# Backplane.net
KiCad netlist of a schematic drawn in EAGLE
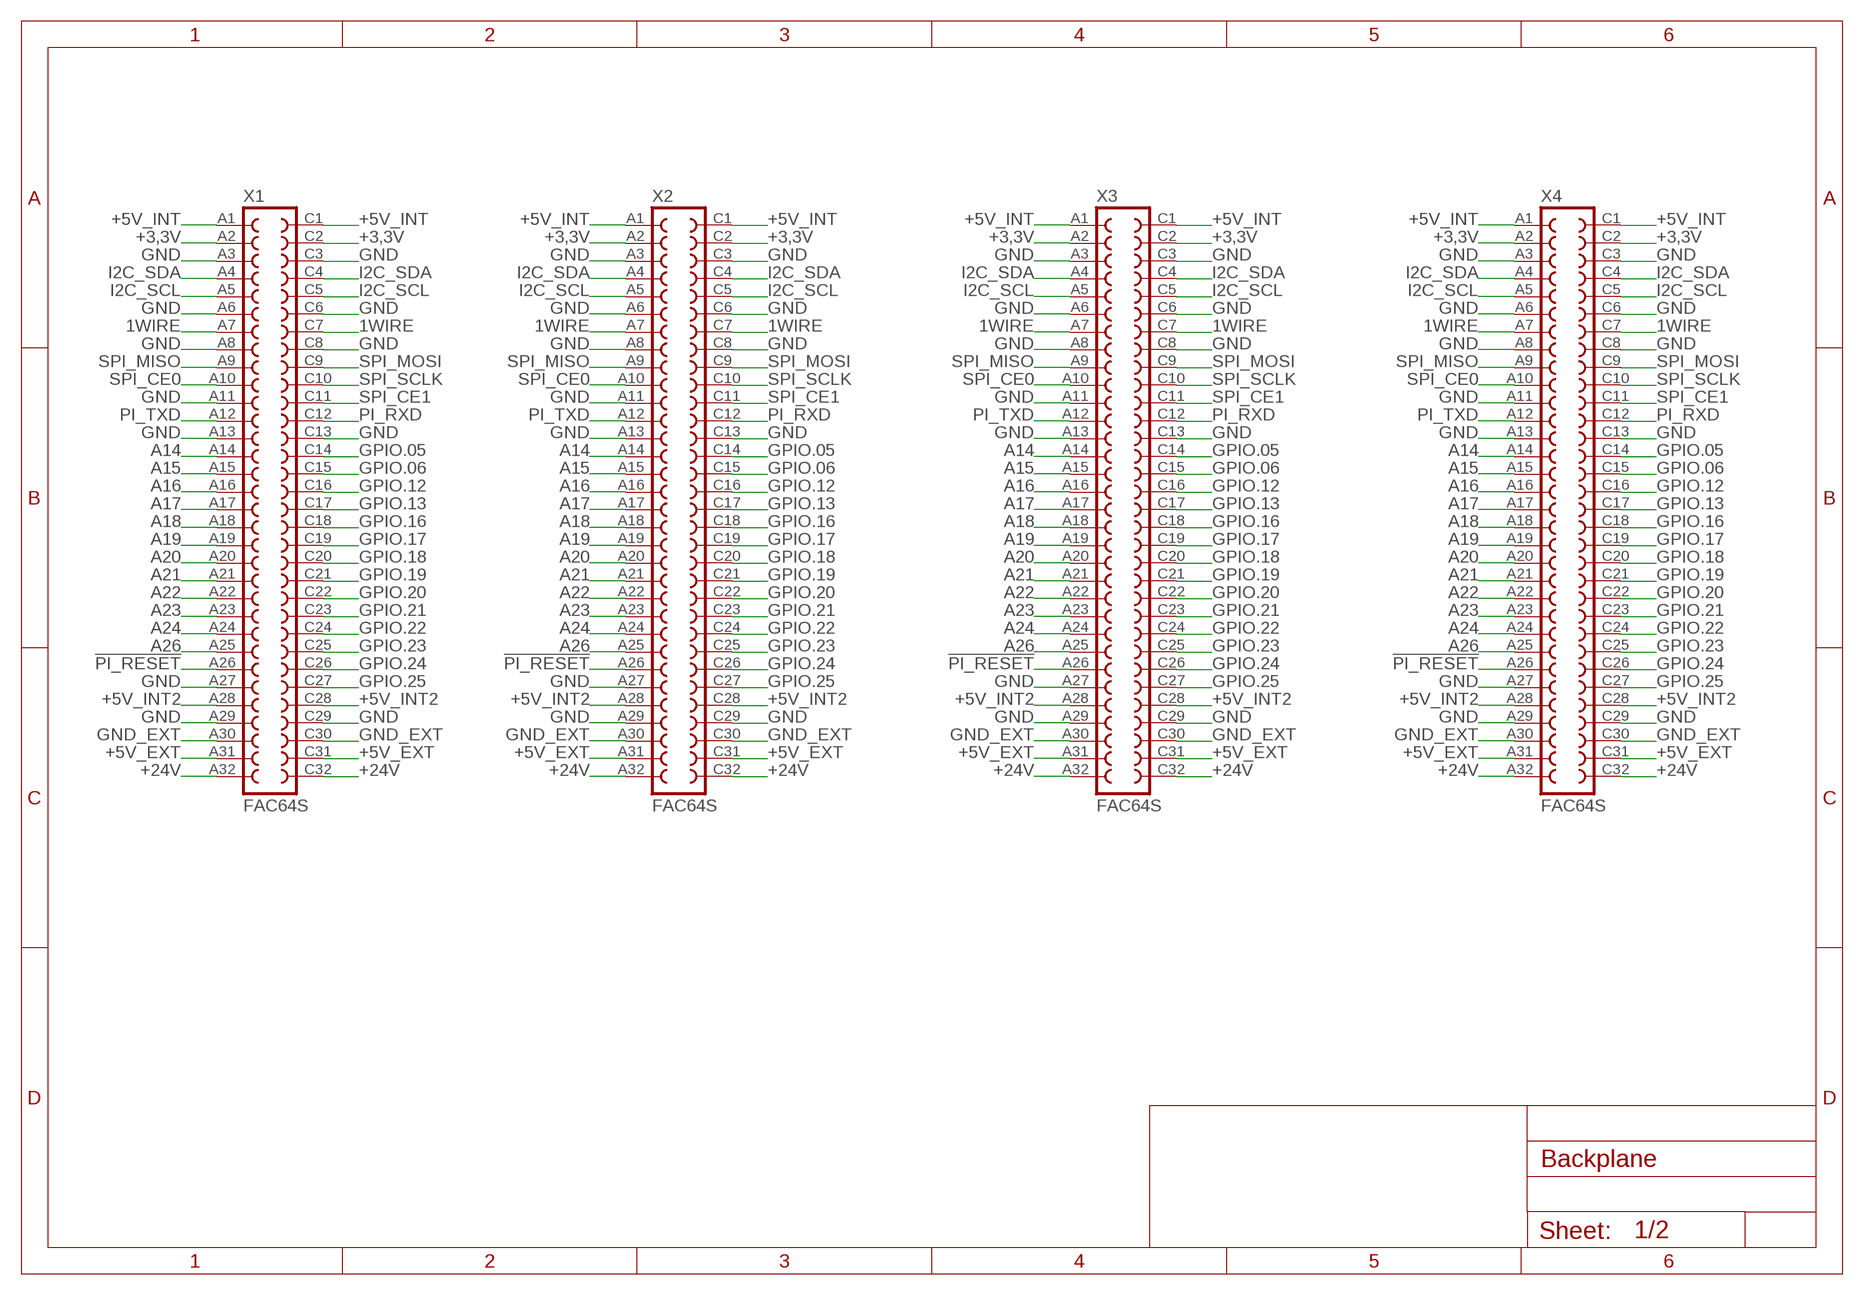
[diagram p0: schematic, sheet 1]
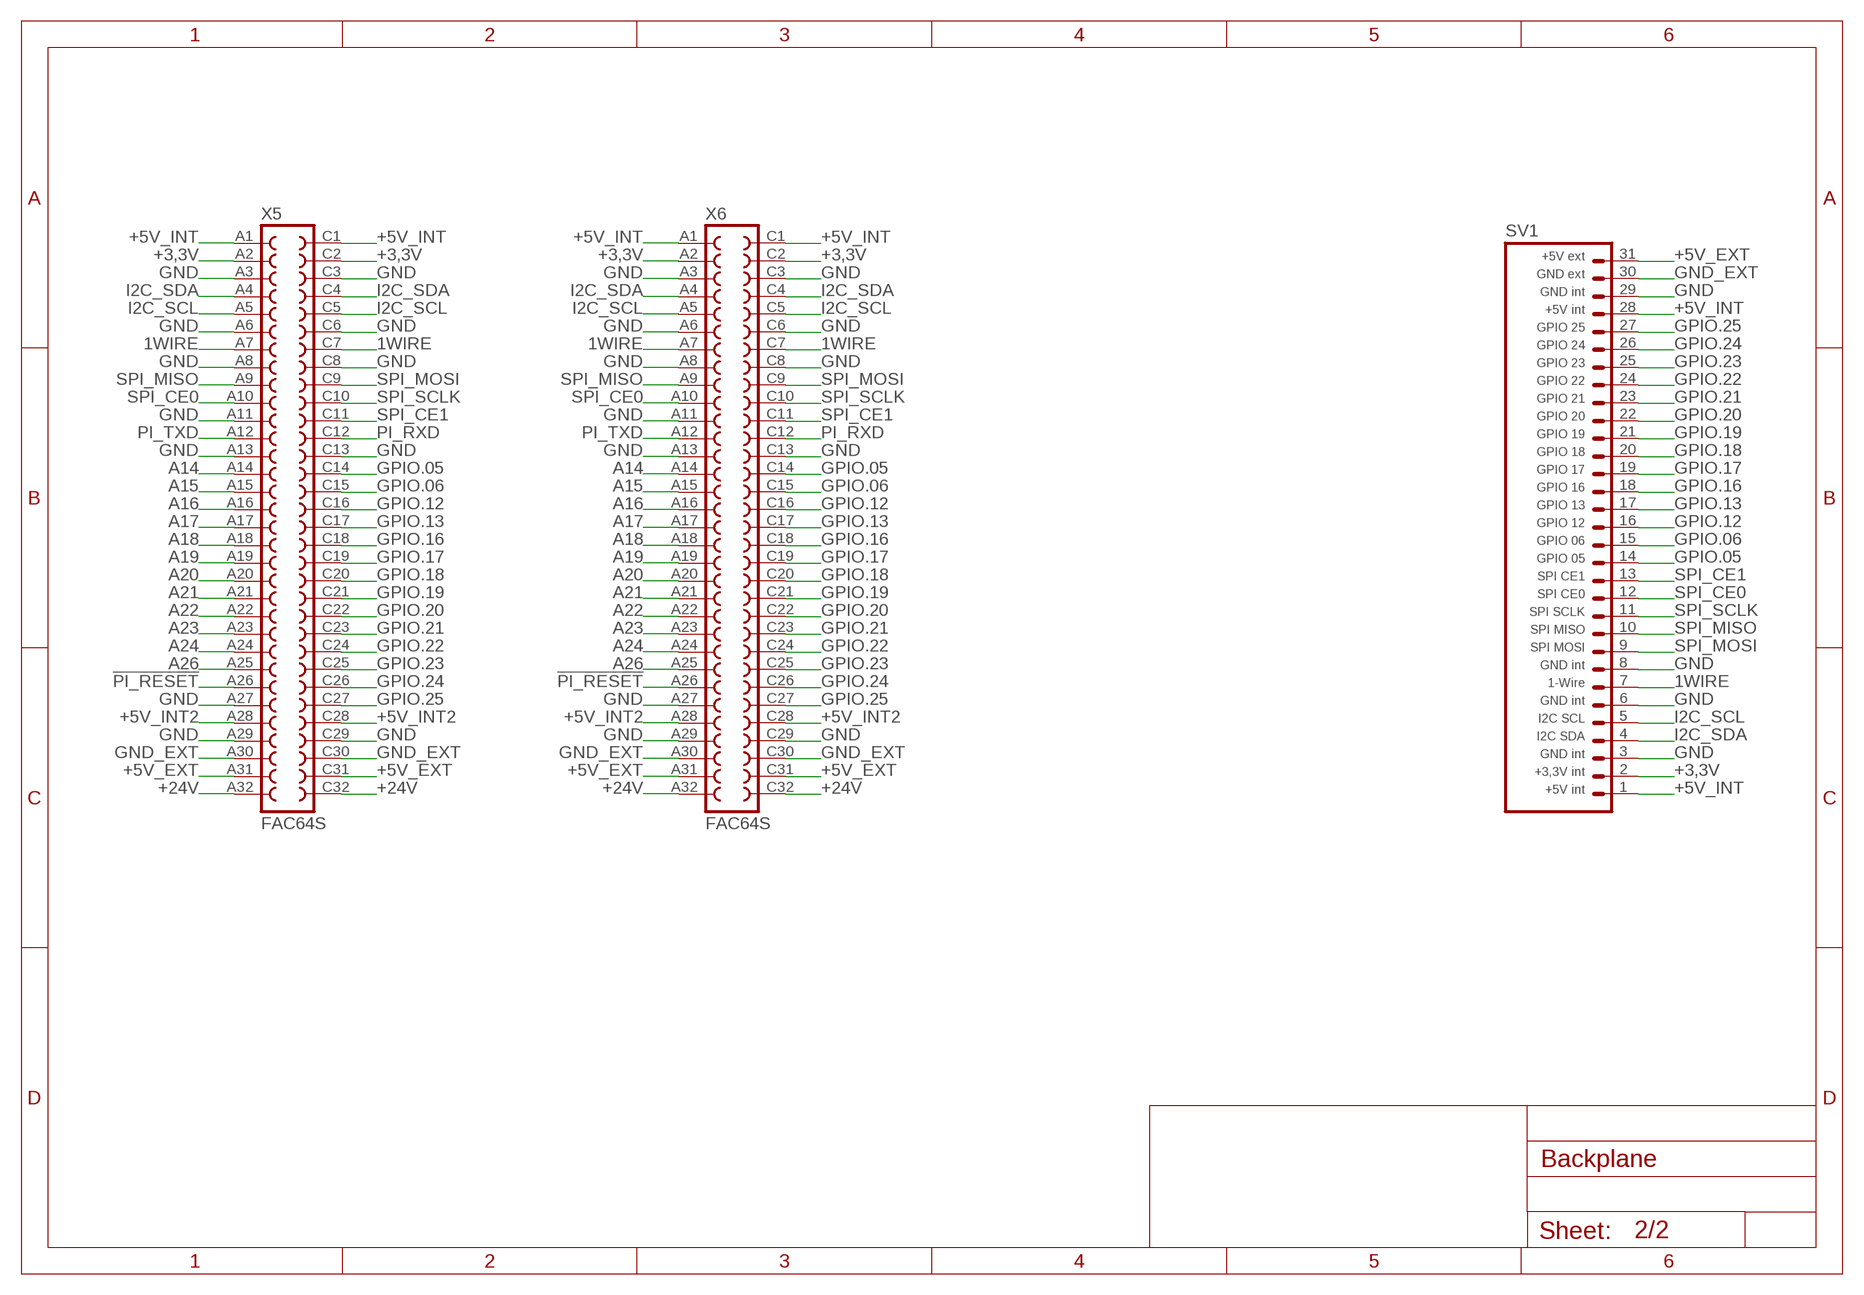
[diagram p1: schematic, sheet 2]

(export (version "E")
  (design (tool "Eeschema 10.0.6"))
  (components
    (comp (ref "X1")
      (value "FAC64S")
      (footprint "eagle-import:FAC64S")
      (libsource (lib "eagle-import") (part "FAC64S"))
    )
    (comp (ref "X2")
      (value "FAC64S")
      (footprint "eagle-import:FAC64S")
      (libsource (lib "eagle-import") (part "FAC64S"))
    )
    (comp (ref "X3")
      (value "FAC64S")
      (footprint "eagle-import:FAC64S")
      (libsource (lib "eagle-import") (part "FAC64S"))
    )
    (comp (ref "X4")
      (value "FAC64S")
      (footprint "eagle-import:FAC64S")
      (libsource (lib "eagle-import") (part "FAC64S"))
    )
    (comp (ref "SV1")
      (value "PLATINENVERBINDER-31SMD-BOTTOM")
      (footprint "eagle-import:PLATINENVERBINDER-31-SMD_BOTTOM")
      (libsource (lib "eagle-import") (part "PLATINENVERBINDER-31SMD-BOTTOM"))
    )
    (comp (ref "X5")
      (value "FAC64S")
      (footprint "eagle-import:FAC64S")
      (libsource (lib "eagle-import") (part "FAC64S"))
    )
    (comp (ref "X6")
      (value "FAC64S")
      (footprint "eagle-import:FAC64S")
      (libsource (lib "eagle-import") (part "FAC64S"))
    )
  )
  (nets
    (net (code "1") (name "+3,3V") (class "Default")
      (node (ref "SV1") (pin "2") (pinfunction "2_2") (pintype "passive"))
      (node (ref "X1") (pin "A2") (pinfunction "A2_A2") (pintype "passive"))
      (node (ref "X1") (pin "C2") (pinfunction "C2_C2") (pintype "passive"))
      (node (ref "X2") (pin "A2") (pinfunction "A2_A2") (pintype "passive"))
      (node (ref "X2") (pin "C2") (pinfunction "C2_C2") (pintype "passive"))
      (node (ref "X3") (pin "A2") (pinfunction "A2_A2") (pintype "passive"))
      (node (ref "X3") (pin "C2") (pinfunction "C2_C2") (pintype "passive"))
      (node (ref "X4") (pin "A2") (pinfunction "A2_A2") (pintype "passive"))
      (node (ref "X4") (pin "C2") (pinfunction "C2_C2") (pintype "passive"))
      (node (ref "X5") (pin "A2") (pinfunction "A2_A2") (pintype "passive"))
      (node (ref "X5") (pin "C2") (pinfunction "C2_C2") (pintype "passive"))
      (node (ref "X6") (pin "A2") (pinfunction "A2_A2") (pintype "passive"))
      (node (ref "X6") (pin "C2") (pinfunction "C2_C2") (pintype "passive"))
    )
    (net (code "2") (name "+5V_EXT") (class "Default")
      (node (ref "SV1") (pin "31") (pinfunction "31_31") (pintype "passive"))
      (node (ref "X1") (pin "A31") (pinfunction "A31_A31") (pintype "passive"))
      (node (ref "X1") (pin "C31") (pinfunction "C31_C31") (pintype "passive"))
      (node (ref "X2") (pin "A31") (pinfunction "A31_A31") (pintype "passive"))
      (node (ref "X2") (pin "C31") (pinfunction "C31_C31") (pintype "passive"))
      (node (ref "X3") (pin "A31") (pinfunction "A31_A31") (pintype "passive"))
      (node (ref "X3") (pin "C31") (pinfunction "C31_C31") (pintype "passive"))
      (node (ref "X4") (pin "A31") (pinfunction "A31_A31") (pintype "passive"))
      (node (ref "X4") (pin "C31") (pinfunction "C31_C31") (pintype "passive"))
      (node (ref "X5") (pin "A31") (pinfunction "A31_A31") (pintype "passive"))
      (node (ref "X5") (pin "C31") (pinfunction "C31_C31") (pintype "passive"))
      (node (ref "X6") (pin "A31") (pinfunction "A31_A31") (pintype "passive"))
      (node (ref "X6") (pin "C31") (pinfunction "C31_C31") (pintype "passive"))
    )
    (net (code "3") (name "+5V_INT") (class "Default")
      (node (ref "SV1") (pin "1") (pinfunction "1_1") (pintype "passive"))
      (node (ref "SV1") (pin "28") (pinfunction "28_28") (pintype "passive"))
      (node (ref "X1") (pin "A1") (pinfunction "A1_A1") (pintype "passive"))
      (node (ref "X1") (pin "C1") (pinfunction "C1_C1") (pintype "passive"))
      (node (ref "X2") (pin "A1") (pinfunction "A1_A1") (pintype "passive"))
      (node (ref "X2") (pin "C1") (pinfunction "C1_C1") (pintype "passive"))
      (node (ref "X3") (pin "A1") (pinfunction "A1_A1") (pintype "passive"))
      (node (ref "X3") (pin "C1") (pinfunction "C1_C1") (pintype "passive"))
      (node (ref "X4") (pin "A1") (pinfunction "A1_A1") (pintype "passive"))
      (node (ref "X4") (pin "C1") (pinfunction "C1_C1") (pintype "passive"))
      (node (ref "X5") (pin "A1") (pinfunction "A1_A1") (pintype "passive"))
      (node (ref "X5") (pin "C1") (pinfunction "C1_C1") (pintype "passive"))
      (node (ref "X6") (pin "A1") (pinfunction "A1_A1") (pintype "passive"))
      (node (ref "X6") (pin "C1") (pinfunction "C1_C1") (pintype "passive"))
    )
    (net (code "4") (name "+5V_INT2") (class "Default")
      (node (ref "X1") (pin "A28") (pinfunction "A28_A28") (pintype "passive"))
      (node (ref "X1") (pin "C28") (pinfunction "C28_C28") (pintype "passive"))
      (node (ref "X2") (pin "A28") (pinfunction "A28_A28") (pintype "passive"))
      (node (ref "X2") (pin "C28") (pinfunction "C28_C28") (pintype "passive"))
      (node (ref "X3") (pin "A28") (pinfunction "A28_A28") (pintype "passive"))
      (node (ref "X3") (pin "C28") (pinfunction "C28_C28") (pintype "passive"))
      (node (ref "X4") (pin "A28") (pinfunction "A28_A28") (pintype "passive"))
      (node (ref "X4") (pin "C28") (pinfunction "C28_C28") (pintype "passive"))
      (node (ref "X5") (pin "A28") (pinfunction "A28_A28") (pintype "passive"))
      (node (ref "X5") (pin "C28") (pinfunction "C28_C28") (pintype "passive"))
      (node (ref "X6") (pin "A28") (pinfunction "A28_A28") (pintype "passive"))
      (node (ref "X6") (pin "C28") (pinfunction "C28_C28") (pintype "passive"))
    )
    (net (code "5") (name "+24V") (class "Default")
      (node (ref "X1") (pin "A32") (pinfunction "A32_A32") (pintype "passive"))
      (node (ref "X1") (pin "C32") (pinfunction "C32_C32") (pintype "passive"))
      (node (ref "X2") (pin "A32") (pinfunction "A32_A32") (pintype "passive"))
      (node (ref "X2") (pin "C32") (pinfunction "C32_C32") (pintype "passive"))
      (node (ref "X3") (pin "A32") (pinfunction "A32_A32") (pintype "passive"))
      (node (ref "X3") (pin "C32") (pinfunction "C32_C32") (pintype "passive"))
      (node (ref "X4") (pin "A32") (pinfunction "A32_A32") (pintype "passive"))
      (node (ref "X4") (pin "C32") (pinfunction "C32_C32") (pintype "passive"))
      (node (ref "X5") (pin "A32") (pinfunction "A32_A32") (pintype "passive"))
      (node (ref "X5") (pin "C32") (pinfunction "C32_C32") (pintype "passive"))
      (node (ref "X6") (pin "A32") (pinfunction "A32_A32") (pintype "passive"))
      (node (ref "X6") (pin "C32") (pinfunction "C32_C32") (pintype "passive"))
    )
    (net (code "6") (name "1WIRE") (class "Default")
      (node (ref "SV1") (pin "7") (pinfunction "7_7") (pintype "passive"))
      (node (ref "X1") (pin "A7") (pinfunction "A7_A7") (pintype "passive"))
      (node (ref "X1") (pin "C7") (pinfunction "C7_C7") (pintype "passive"))
      (node (ref "X2") (pin "A7") (pinfunction "A7_A7") (pintype "passive"))
      (node (ref "X2") (pin "C7") (pinfunction "C7_C7") (pintype "passive"))
      (node (ref "X3") (pin "A7") (pinfunction "A7_A7") (pintype "passive"))
      (node (ref "X3") (pin "C7") (pinfunction "C7_C7") (pintype "passive"))
      (node (ref "X4") (pin "A7") (pinfunction "A7_A7") (pintype "passive"))
      (node (ref "X4") (pin "C7") (pinfunction "C7_C7") (pintype "passive"))
      (node (ref "X5") (pin "A7") (pinfunction "A7_A7") (pintype "passive"))
      (node (ref "X5") (pin "C7") (pinfunction "C7_C7") (pintype "passive"))
      (node (ref "X6") (pin "A7") (pinfunction "A7_A7") (pintype "passive"))
      (node (ref "X6") (pin "C7") (pinfunction "C7_C7") (pintype "passive"))
    )
    (net (code "7") (name "A14") (class "Default")
      (node (ref "X1") (pin "A14") (pinfunction "A14_A14") (pintype "passive"))
      (node (ref "X2") (pin "A14") (pinfunction "A14_A14") (pintype "passive"))
      (node (ref "X3") (pin "A14") (pinfunction "A14_A14") (pintype "passive"))
      (node (ref "X4") (pin "A14") (pinfunction "A14_A14") (pintype "passive"))
      (node (ref "X5") (pin "A14") (pinfunction "A14_A14") (pintype "passive"))
      (node (ref "X6") (pin "A14") (pinfunction "A14_A14") (pintype "passive"))
    )
    (net (code "8") (name "A15") (class "Default")
      (node (ref "X1") (pin "A15") (pinfunction "A15_A15") (pintype "passive"))
      (node (ref "X2") (pin "A15") (pinfunction "A15_A15") (pintype "passive"))
      (node (ref "X3") (pin "A15") (pinfunction "A15_A15") (pintype "passive"))
      (node (ref "X4") (pin "A15") (pinfunction "A15_A15") (pintype "passive"))
      (node (ref "X5") (pin "A15") (pinfunction "A15_A15") (pintype "passive"))
      (node (ref "X6") (pin "A15") (pinfunction "A15_A15") (pintype "passive"))
    )
    (net (code "9") (name "A16") (class "Default")
      (node (ref "X1") (pin "A16") (pinfunction "A16_A16") (pintype "passive"))
      (node (ref "X2") (pin "A16") (pinfunction "A16_A16") (pintype "passive"))
      (node (ref "X3") (pin "A16") (pinfunction "A16_A16") (pintype "passive"))
      (node (ref "X4") (pin "A16") (pinfunction "A16_A16") (pintype "passive"))
      (node (ref "X5") (pin "A16") (pinfunction "A16_A16") (pintype "passive"))
      (node (ref "X6") (pin "A16") (pinfunction "A16_A16") (pintype "passive"))
    )
    (net (code "10") (name "A17") (class "Default")
      (node (ref "X1") (pin "A17") (pinfunction "A17_A17") (pintype "passive"))
      (node (ref "X2") (pin "A17") (pinfunction "A17_A17") (pintype "passive"))
      (node (ref "X3") (pin "A17") (pinfunction "A17_A17") (pintype "passive"))
      (node (ref "X4") (pin "A17") (pinfunction "A17_A17") (pintype "passive"))
      (node (ref "X5") (pin "A17") (pinfunction "A17_A17") (pintype "passive"))
      (node (ref "X6") (pin "A17") (pinfunction "A17_A17") (pintype "passive"))
    )
    (net (code "11") (name "A18") (class "Default")
      (node (ref "X1") (pin "A18") (pinfunction "A18_A18") (pintype "passive"))
      (node (ref "X2") (pin "A18") (pinfunction "A18_A18") (pintype "passive"))
      (node (ref "X3") (pin "A18") (pinfunction "A18_A18") (pintype "passive"))
      (node (ref "X4") (pin "A18") (pinfunction "A18_A18") (pintype "passive"))
      (node (ref "X5") (pin "A18") (pinfunction "A18_A18") (pintype "passive"))
      (node (ref "X6") (pin "A18") (pinfunction "A18_A18") (pintype "passive"))
    )
    (net (code "12") (name "A19") (class "Default")
      (node (ref "X1") (pin "A19") (pinfunction "A19_A19") (pintype "passive"))
      (node (ref "X2") (pin "A19") (pinfunction "A19_A19") (pintype "passive"))
      (node (ref "X3") (pin "A19") (pinfunction "A19_A19") (pintype "passive"))
      (node (ref "X4") (pin "A19") (pinfunction "A19_A19") (pintype "passive"))
      (node (ref "X5") (pin "A19") (pinfunction "A19_A19") (pintype "passive"))
      (node (ref "X6") (pin "A19") (pinfunction "A19_A19") (pintype "passive"))
    )
    (net (code "13") (name "A20") (class "Default")
      (node (ref "X1") (pin "A20") (pinfunction "A20_A20") (pintype "passive"))
      (node (ref "X2") (pin "A20") (pinfunction "A20_A20") (pintype "passive"))
      (node (ref "X3") (pin "A20") (pinfunction "A20_A20") (pintype "passive"))
      (node (ref "X4") (pin "A20") (pinfunction "A20_A20") (pintype "passive"))
      (node (ref "X5") (pin "A20") (pinfunction "A20_A20") (pintype "passive"))
      (node (ref "X6") (pin "A20") (pinfunction "A20_A20") (pintype "passive"))
    )
    (net (code "14") (name "A21") (class "Default")
      (node (ref "X1") (pin "A21") (pinfunction "A21_A21") (pintype "passive"))
      (node (ref "X2") (pin "A21") (pinfunction "A21_A21") (pintype "passive"))
      (node (ref "X3") (pin "A21") (pinfunction "A21_A21") (pintype "passive"))
      (node (ref "X4") (pin "A21") (pinfunction "A21_A21") (pintype "passive"))
      (node (ref "X5") (pin "A21") (pinfunction "A21_A21") (pintype "passive"))
      (node (ref "X6") (pin "A21") (pinfunction "A21_A21") (pintype "passive"))
    )
    (net (code "15") (name "A22") (class "Default")
      (node (ref "X1") (pin "A22") (pinfunction "A22_A22") (pintype "passive"))
      (node (ref "X2") (pin "A22") (pinfunction "A22_A22") (pintype "passive"))
      (node (ref "X3") (pin "A22") (pinfunction "A22_A22") (pintype "passive"))
      (node (ref "X4") (pin "A22") (pinfunction "A22_A22") (pintype "passive"))
      (node (ref "X5") (pin "A22") (pinfunction "A22_A22") (pintype "passive"))
      (node (ref "X6") (pin "A22") (pinfunction "A22_A22") (pintype "passive"))
    )
    (net (code "16") (name "A23") (class "Default")
      (node (ref "X1") (pin "A23") (pinfunction "A23_A23") (pintype "passive"))
      (node (ref "X2") (pin "A23") (pinfunction "A23_A23") (pintype "passive"))
      (node (ref "X3") (pin "A23") (pinfunction "A23_A23") (pintype "passive"))
      (node (ref "X4") (pin "A23") (pinfunction "A23_A23") (pintype "passive"))
      (node (ref "X5") (pin "A23") (pinfunction "A23_A23") (pintype "passive"))
      (node (ref "X6") (pin "A23") (pinfunction "A23_A23") (pintype "passive"))
    )
    (net (code "17") (name "A24") (class "Default")
      (node (ref "X1") (pin "A24") (pinfunction "A24_A24") (pintype "passive"))
      (node (ref "X2") (pin "A24") (pinfunction "A24_A24") (pintype "passive"))
      (node (ref "X3") (pin "A24") (pinfunction "A24_A24") (pintype "passive"))
      (node (ref "X4") (pin "A24") (pinfunction "A24_A24") (pintype "passive"))
      (node (ref "X5") (pin "A24") (pinfunction "A24_A24") (pintype "passive"))
      (node (ref "X6") (pin "A24") (pinfunction "A24_A24") (pintype "passive"))
    )
    (net (code "18") (name "A26") (class "Default")
      (node (ref "X1") (pin "A25") (pinfunction "A25_A25") (pintype "passive"))
      (node (ref "X2") (pin "A25") (pinfunction "A25_A25") (pintype "passive"))
      (node (ref "X3") (pin "A25") (pinfunction "A25_A25") (pintype "passive"))
      (node (ref "X4") (pin "A25") (pinfunction "A25_A25") (pintype "passive"))
      (node (ref "X5") (pin "A25") (pinfunction "A25_A25") (pintype "passive"))
      (node (ref "X6") (pin "A25") (pinfunction "A25_A25") (pintype "passive"))
    )
    (net (code "19") (name "GND") (class "Default")
      (node (ref "SV1") (pin "29") (pinfunction "29_29") (pintype "passive"))
      (node (ref "SV1") (pin "3") (pinfunction "3_3") (pintype "passive"))
      (node (ref "SV1") (pin "6") (pinfunction "6_6") (pintype "passive"))
      (node (ref "SV1") (pin "8") (pinfunction "8_8") (pintype "passive"))
      (node (ref "X1") (pin "A11") (pinfunction "A11_A11") (pintype "passive"))
      (node (ref "X1") (pin "A13") (pinfunction "A13_A13") (pintype "passive"))
      (node (ref "X1") (pin "A27") (pinfunction "A27_A27") (pintype "passive"))
      (node (ref "X1") (pin "A29") (pinfunction "A29_A29") (pintype "passive"))
      (node (ref "X1") (pin "A3") (pinfunction "A3_A3") (pintype "passive"))
      (node (ref "X1") (pin "A6") (pinfunction "A6_A6") (pintype "passive"))
      (node (ref "X1") (pin "A8") (pinfunction "A8_A8") (pintype "passive"))
      (node (ref "X1") (pin "C13") (pinfunction "C13_C13") (pintype "passive"))
      (node (ref "X1") (pin "C29") (pinfunction "C29_C29") (pintype "passive"))
      (node (ref "X1") (pin "C3") (pinfunction "C3_C3") (pintype "passive"))
      (node (ref "X1") (pin "C6") (pinfunction "C6_C6") (pintype "passive"))
      (node (ref "X1") (pin "C8") (pinfunction "C8_C8") (pintype "passive"))
      (node (ref "X2") (pin "A11") (pinfunction "A11_A11") (pintype "passive"))
      (node (ref "X2") (pin "A13") (pinfunction "A13_A13") (pintype "passive"))
      (node (ref "X2") (pin "A27") (pinfunction "A27_A27") (pintype "passive"))
      (node (ref "X2") (pin "A29") (pinfunction "A29_A29") (pintype "passive"))
      (node (ref "X2") (pin "A3") (pinfunction "A3_A3") (pintype "passive"))
      (node (ref "X2") (pin "A6") (pinfunction "A6_A6") (pintype "passive"))
      (node (ref "X2") (pin "A8") (pinfunction "A8_A8") (pintype "passive"))
      (node (ref "X2") (pin "C13") (pinfunction "C13_C13") (pintype "passive"))
      (node (ref "X2") (pin "C29") (pinfunction "C29_C29") (pintype "passive"))
      (node (ref "X2") (pin "C3") (pinfunction "C3_C3") (pintype "passive"))
      (node (ref "X2") (pin "C6") (pinfunction "C6_C6") (pintype "passive"))
      (node (ref "X2") (pin "C8") (pinfunction "C8_C8") (pintype "passive"))
      (node (ref "X3") (pin "A11") (pinfunction "A11_A11") (pintype "passive"))
      (node (ref "X3") (pin "A13") (pinfunction "A13_A13") (pintype "passive"))
      (node (ref "X3") (pin "A27") (pinfunction "A27_A27") (pintype "passive"))
      (node (ref "X3") (pin "A29") (pinfunction "A29_A29") (pintype "passive"))
      (node (ref "X3") (pin "A3") (pinfunction "A3_A3") (pintype "passive"))
      (node (ref "X3") (pin "A6") (pinfunction "A6_A6") (pintype "passive"))
      (node (ref "X3") (pin "A8") (pinfunction "A8_A8") (pintype "passive"))
      (node (ref "X3") (pin "C13") (pinfunction "C13_C13") (pintype "passive"))
      (node (ref "X3") (pin "C29") (pinfunction "C29_C29") (pintype "passive"))
      (node (ref "X3") (pin "C3") (pinfunction "C3_C3") (pintype "passive"))
      (node (ref "X3") (pin "C6") (pinfunction "C6_C6") (pintype "passive"))
      (node (ref "X3") (pin "C8") (pinfunction "C8_C8") (pintype "passive"))
      (node (ref "X4") (pin "A11") (pinfunction "A11_A11") (pintype "passive"))
      (node (ref "X4") (pin "A13") (pinfunction "A13_A13") (pintype "passive"))
      (node (ref "X4") (pin "A27") (pinfunction "A27_A27") (pintype "passive"))
      (node (ref "X4") (pin "A29") (pinfunction "A29_A29") (pintype "passive"))
      (node (ref "X4") (pin "A3") (pinfunction "A3_A3") (pintype "passive"))
      (node (ref "X4") (pin "A6") (pinfunction "A6_A6") (pintype "passive"))
      (node (ref "X4") (pin "A8") (pinfunction "A8_A8") (pintype "passive"))
      (node (ref "X4") (pin "C13") (pinfunction "C13_C13") (pintype "passive"))
      (node (ref "X4") (pin "C29") (pinfunction "C29_C29") (pintype "passive"))
      (node (ref "X4") (pin "C3") (pinfunction "C3_C3") (pintype "passive"))
      (node (ref "X4") (pin "C6") (pinfunction "C6_C6") (pintype "passive"))
      (node (ref "X4") (pin "C8") (pinfunction "C8_C8") (pintype "passive"))
      (node (ref "X5") (pin "A11") (pinfunction "A11_A11") (pintype "passive"))
      (node (ref "X5") (pin "A13") (pinfunction "A13_A13") (pintype "passive"))
      (node (ref "X5") (pin "A27") (pinfunction "A27_A27") (pintype "passive"))
      (node (ref "X5") (pin "A29") (pinfunction "A29_A29") (pintype "passive"))
      (node (ref "X5") (pin "A3") (pinfunction "A3_A3") (pintype "passive"))
      (node (ref "X5") (pin "A6") (pinfunction "A6_A6") (pintype "passive"))
      (node (ref "X5") (pin "A8") (pinfunction "A8_A8") (pintype "passive"))
      (node (ref "X5") (pin "C13") (pinfunction "C13_C13") (pintype "passive"))
      (node (ref "X5") (pin "C29") (pinfunction "C29_C29") (pintype "passive"))
      (node (ref "X5") (pin "C3") (pinfunction "C3_C3") (pintype "passive"))
      (node (ref "X5") (pin "C6") (pinfunction "C6_C6") (pintype "passive"))
      (node (ref "X5") (pin "C8") (pinfunction "C8_C8") (pintype "passive"))
      (node (ref "X6") (pin "A11") (pinfunction "A11_A11") (pintype "passive"))
      (node (ref "X6") (pin "A13") (pinfunction "A13_A13") (pintype "passive"))
      (node (ref "X6") (pin "A27") (pinfunction "A27_A27") (pintype "passive"))
      (node (ref "X6") (pin "A29") (pinfunction "A29_A29") (pintype "passive"))
      (node (ref "X6") (pin "A3") (pinfunction "A3_A3") (pintype "passive"))
      (node (ref "X6") (pin "A6") (pinfunction "A6_A6") (pintype "passive"))
      (node (ref "X6") (pin "A8") (pinfunction "A8_A8") (pintype "passive"))
      (node (ref "X6") (pin "C13") (pinfunction "C13_C13") (pintype "passive"))
      (node (ref "X6") (pin "C29") (pinfunction "C29_C29") (pintype "passive"))
      (node (ref "X6") (pin "C3") (pinfunction "C3_C3") (pintype "passive"))
      (node (ref "X6") (pin "C6") (pinfunction "C6_C6") (pintype "passive"))
      (node (ref "X6") (pin "C8") (pinfunction "C8_C8") (pintype "passive"))
    )
    (net (code "20") (name "GND_EXT") (class "Default")
      (node (ref "SV1") (pin "30") (pinfunction "30_30") (pintype "passive"))
      (node (ref "X1") (pin "A30") (pinfunction "A30_A30") (pintype "passive"))
      (node (ref "X1") (pin "C30") (pinfunction "C30_C30") (pintype "passive"))
      (node (ref "X2") (pin "A30") (pinfunction "A30_A30") (pintype "passive"))
      (node (ref "X2") (pin "C30") (pinfunction "C30_C30") (pintype "passive"))
      (node (ref "X3") (pin "A30") (pinfunction "A30_A30") (pintype "passive"))
      (node (ref "X3") (pin "C30") (pinfunction "C30_C30") (pintype "passive"))
      (node (ref "X4") (pin "A30") (pinfunction "A30_A30") (pintype "passive"))
      (node (ref "X4") (pin "C30") (pinfunction "C30_C30") (pintype "passive"))
      (node (ref "X5") (pin "A30") (pinfunction "A30_A30") (pintype "passive"))
      (node (ref "X5") (pin "C30") (pinfunction "C30_C30") (pintype "passive"))
      (node (ref "X6") (pin "A30") (pinfunction "A30_A30") (pintype "passive"))
      (node (ref "X6") (pin "C30") (pinfunction "C30_C30") (pintype "passive"))
    )
    (net (code "21") (name "GPIO.05") (class "Default")
      (node (ref "SV1") (pin "14") (pinfunction "14_14") (pintype "passive"))
      (node (ref "X1") (pin "C14") (pinfunction "C14_C14") (pintype "passive"))
      (node (ref "X2") (pin "C14") (pinfunction "C14_C14") (pintype "passive"))
      (node (ref "X3") (pin "C14") (pinfunction "C14_C14") (pintype "passive"))
      (node (ref "X4") (pin "C14") (pinfunction "C14_C14") (pintype "passive"))
      (node (ref "X5") (pin "C14") (pinfunction "C14_C14") (pintype "passive"))
      (node (ref "X6") (pin "C14") (pinfunction "C14_C14") (pintype "passive"))
    )
    (net (code "22") (name "GPIO.06") (class "Default")
      (node (ref "SV1") (pin "15") (pinfunction "15_15") (pintype "passive"))
      (node (ref "X1") (pin "C15") (pinfunction "C15_C15") (pintype "passive"))
      (node (ref "X2") (pin "C15") (pinfunction "C15_C15") (pintype "passive"))
      (node (ref "X3") (pin "C15") (pinfunction "C15_C15") (pintype "passive"))
      (node (ref "X4") (pin "C15") (pinfunction "C15_C15") (pintype "passive"))
      (node (ref "X5") (pin "C15") (pinfunction "C15_C15") (pintype "passive"))
      (node (ref "X6") (pin "C15") (pinfunction "C15_C15") (pintype "passive"))
    )
    (net (code "23") (name "GPIO.12") (class "Default")
      (node (ref "SV1") (pin "16") (pinfunction "16_16") (pintype "passive"))
      (node (ref "X1") (pin "C16") (pinfunction "C16_C16") (pintype "passive"))
      (node (ref "X2") (pin "C16") (pinfunction "C16_C16") (pintype "passive"))
      (node (ref "X3") (pin "C16") (pinfunction "C16_C16") (pintype "passive"))
      (node (ref "X4") (pin "C16") (pinfunction "C16_C16") (pintype "passive"))
      (node (ref "X5") (pin "C16") (pinfunction "C16_C16") (pintype "passive"))
      (node (ref "X6") (pin "C16") (pinfunction "C16_C16") (pintype "passive"))
    )
    (net (code "24") (name "GPIO.13") (class "Default")
      (node (ref "SV1") (pin "17") (pinfunction "17_17") (pintype "passive"))
      (node (ref "X1") (pin "C17") (pinfunction "C17_C17") (pintype "passive"))
      (node (ref "X2") (pin "C17") (pinfunction "C17_C17") (pintype "passive"))
      (node (ref "X3") (pin "C17") (pinfunction "C17_C17") (pintype "passive"))
      (node (ref "X4") (pin "C17") (pinfunction "C17_C17") (pintype "passive"))
      (node (ref "X5") (pin "C17") (pinfunction "C17_C17") (pintype "passive"))
      (node (ref "X6") (pin "C17") (pinfunction "C17_C17") (pintype "passive"))
    )
    (net (code "25") (name "GPIO.16") (class "Default")
      (node (ref "SV1") (pin "18") (pinfunction "18_18") (pintype "passive"))
      (node (ref "X1") (pin "C18") (pinfunction "C18_C18") (pintype "passive"))
      (node (ref "X2") (pin "C18") (pinfunction "C18_C18") (pintype "passive"))
      (node (ref "X3") (pin "C18") (pinfunction "C18_C18") (pintype "passive"))
      (node (ref "X4") (pin "C18") (pinfunction "C18_C18") (pintype "passive"))
      (node (ref "X5") (pin "C18") (pinfunction "C18_C18") (pintype "passive"))
      (node (ref "X6") (pin "C18") (pinfunction "C18_C18") (pintype "passive"))
    )
    (net (code "26") (name "GPIO.17") (class "Default")
      (node (ref "SV1") (pin "19") (pinfunction "19_19") (pintype "passive"))
      (node (ref "X1") (pin "C19") (pinfunction "C19_C19") (pintype "passive"))
      (node (ref "X2") (pin "C19") (pinfunction "C19_C19") (pintype "passive"))
      (node (ref "X3") (pin "C19") (pinfunction "C19_C19") (pintype "passive"))
      (node (ref "X4") (pin "C19") (pinfunction "C19_C19") (pintype "passive"))
      (node (ref "X5") (pin "C19") (pinfunction "C19_C19") (pintype "passive"))
      (node (ref "X6") (pin "C19") (pinfunction "C19_C19") (pintype "passive"))
    )
    (net (code "27") (name "GPIO.18") (class "Default")
      (node (ref "SV1") (pin "20") (pinfunction "20_20") (pintype "passive"))
      (node (ref "X1") (pin "C20") (pinfunction "C20_C20") (pintype "passive"))
      (node (ref "X2") (pin "C20") (pinfunction "C20_C20") (pintype "passive"))
      (node (ref "X3") (pin "C20") (pinfunction "C20_C20") (pintype "passive"))
      (node (ref "X4") (pin "C20") (pinfunction "C20_C20") (pintype "passive"))
      (node (ref "X5") (pin "C20") (pinfunction "C20_C20") (pintype "passive"))
      (node (ref "X6") (pin "C20") (pinfunction "C20_C20") (pintype "passive"))
    )
    (net (code "28") (name "GPIO.19") (class "Default")
      (node (ref "SV1") (pin "21") (pinfunction "21_21") (pintype "passive"))
      (node (ref "X1") (pin "C21") (pinfunction "C21_C21") (pintype "passive"))
      (node (ref "X2") (pin "C21") (pinfunction "C21_C21") (pintype "passive"))
      (node (ref "X3") (pin "C21") (pinfunction "C21_C21") (pintype "passive"))
      (node (ref "X4") (pin "C21") (pinfunction "C21_C21") (pintype "passive"))
      (node (ref "X5") (pin "C21") (pinfunction "C21_C21") (pintype "passive"))
      (node (ref "X6") (pin "C21") (pinfunction "C21_C21") (pintype "passive"))
    )
    (net (code "29") (name "GPIO.20") (class "Default")
      (node (ref "SV1") (pin "22") (pinfunction "22_22") (pintype "passive"))
      (node (ref "X1") (pin "C22") (pinfunction "C22_C22") (pintype "passive"))
      (node (ref "X2") (pin "C22") (pinfunction "C22_C22") (pintype "passive"))
      (node (ref "X3") (pin "C22") (pinfunction "C22_C22") (pintype "passive"))
      (node (ref "X4") (pin "C22") (pinfunction "C22_C22") (pintype "passive"))
      (node (ref "X5") (pin "C22") (pinfunction "C22_C22") (pintype "passive"))
      (node (ref "X6") (pin "C22") (pinfunction "C22_C22") (pintype "passive"))
    )
    (net (code "30") (name "GPIO.21") (class "Default")
      (node (ref "SV1") (pin "23") (pinfunction "23_23") (pintype "passive"))
      (node (ref "X1") (pin "C23") (pinfunction "C23_C23") (pintype "passive"))
      (node (ref "X2") (pin "C23") (pinfunction "C23_C23") (pintype "passive"))
      (node (ref "X3") (pin "C23") (pinfunction "C23_C23") (pintype "passive"))
      (node (ref "X4") (pin "C23") (pinfunction "C23_C23") (pintype "passive"))
      (node (ref "X5") (pin "C23") (pinfunction "C23_C23") (pintype "passive"))
      (node (ref "X6") (pin "C23") (pinfunction "C23_C23") (pintype "passive"))
    )
    (net (code "31") (name "GPIO.22") (class "Default")
      (node (ref "SV1") (pin "24") (pinfunction "24_24") (pintype "passive"))
      (node (ref "X1") (pin "C24") (pinfunction "C24_C24") (pintype "passive"))
      (node (ref "X2") (pin "C24") (pinfunction "C24_C24") (pintype "passive"))
      (node (ref "X3") (pin "C24") (pinfunction "C24_C24") (pintype "passive"))
      (node (ref "X4") (pin "C24") (pinfunction "C24_C24") (pintype "passive"))
      (node (ref "X5") (pin "C24") (pinfunction "C24_C24") (pintype "passive"))
      (node (ref "X6") (pin "C24") (pinfunction "C24_C24") (pintype "passive"))
    )
    (net (code "32") (name "GPIO.23") (class "Default")
      (node (ref "SV1") (pin "25") (pinfunction "25_25") (pintype "passive"))
      (node (ref "X1") (pin "C25") (pinfunction "C25_C25") (pintype "passive"))
      (node (ref "X2") (pin "C25") (pinfunction "C25_C25") (pintype "passive"))
      (node (ref "X3") (pin "C25") (pinfunction "C25_C25") (pintype "passive"))
      (node (ref "X4") (pin "C25") (pinfunction "C25_C25") (pintype "passive"))
      (node (ref "X5") (pin "C25") (pinfunction "C25_C25") (pintype "passive"))
      (node (ref "X6") (pin "C25") (pinfunction "C25_C25") (pintype "passive"))
    )
    (net (code "33") (name "GPIO.24") (class "Default")
      (node (ref "SV1") (pin "26") (pinfunction "26_26") (pintype "passive"))
      (node (ref "X1") (pin "C26") (pinfunction "C26_C26") (pintype "passive"))
      (node (ref "X2") (pin "C26") (pinfunction "C26_C26") (pintype "passive"))
      (node (ref "X3") (pin "C26") (pinfunction "C26_C26") (pintype "passive"))
      (node (ref "X4") (pin "C26") (pinfunction "C26_C26") (pintype "passive"))
      (node (ref "X5") (pin "C26") (pinfunction "C26_C26") (pintype "passive"))
      (node (ref "X6") (pin "C26") (pinfunction "C26_C26") (pintype "passive"))
    )
    (net (code "34") (name "GPIO.25") (class "Default")
      (node (ref "SV1") (pin "27") (pinfunction "27_27") (pintype "passive"))
      (node (ref "X1") (pin "C27") (pinfunction "C27_C27") (pintype "passive"))
      (node (ref "X2") (pin "C27") (pinfunction "C27_C27") (pintype "passive"))
      (node (ref "X3") (pin "C27") (pinfunction "C27_C27") (pintype "passive"))
      (node (ref "X4") (pin "C27") (pinfunction "C27_C27") (pintype "passive"))
      (node (ref "X5") (pin "C27") (pinfunction "C27_C27") (pintype "passive"))
      (node (ref "X6") (pin "C27") (pinfunction "C27_C27") (pintype "passive"))
    )
    (net (code "35") (name "I2C_SCL") (class "Default")
      (node (ref "SV1") (pin "5") (pinfunction "5_5") (pintype "passive"))
      (node (ref "X1") (pin "A5") (pinfunction "A5_A5") (pintype "passive"))
      (node (ref "X1") (pin "C5") (pinfunction "C5_C5") (pintype "passive"))
      (node (ref "X2") (pin "A5") (pinfunction "A5_A5") (pintype "passive"))
      (node (ref "X2") (pin "C5") (pinfunction "C5_C5") (pintype "passive"))
      (node (ref "X3") (pin "A5") (pinfunction "A5_A5") (pintype "passive"))
      (node (ref "X3") (pin "C5") (pinfunction "C5_C5") (pintype "passive"))
      (node (ref "X4") (pin "A5") (pinfunction "A5_A5") (pintype "passive"))
      (node (ref "X4") (pin "C5") (pinfunction "C5_C5") (pintype "passive"))
      (node (ref "X5") (pin "A5") (pinfunction "A5_A5") (pintype "passive"))
      (node (ref "X5") (pin "C5") (pinfunction "C5_C5") (pintype "passive"))
      (node (ref "X6") (pin "A5") (pinfunction "A5_A5") (pintype "passive"))
      (node (ref "X6") (pin "C5") (pinfunction "C5_C5") (pintype "passive"))
    )
    (net (code "36") (name "I2C_SDA") (class "Default")
      (node (ref "SV1") (pin "4") (pinfunction "4_4") (pintype "passive"))
      (node (ref "X1") (pin "A4") (pinfunction "A4_A4") (pintype "passive"))
      (node (ref "X1") (pin "C4") (pinfunction "C4_C4") (pintype "passive"))
      (node (ref "X2") (pin "A4") (pinfunction "A4_A4") (pintype "passive"))
      (node (ref "X2") (pin "C4") (pinfunction "C4_C4") (pintype "passive"))
      (node (ref "X3") (pin "A4") (pinfunction "A4_A4") (pintype "passive"))
      (node (ref "X3") (pin "C4") (pinfunction "C4_C4") (pintype "passive"))
      (node (ref "X4") (pin "A4") (pinfunction "A4_A4") (pintype "passive"))
      (node (ref "X4") (pin "C4") (pinfunction "C4_C4") (pintype "passive"))
      (node (ref "X5") (pin "A4") (pinfunction "A4_A4") (pintype "passive"))
      (node (ref "X5") (pin "C4") (pinfunction "C4_C4") (pintype "passive"))
      (node (ref "X6") (pin "A4") (pinfunction "A4_A4") (pintype "passive"))
      (node (ref "X6") (pin "C4") (pinfunction "C4_C4") (pintype "passive"))
    )
    (net (code "37") (name "PI_RXD") (class "Default")
      (node (ref "X1") (pin "C12") (pinfunction "C12_C12") (pintype "passive"))
      (node (ref "X2") (pin "C12") (pinfunction "C12_C12") (pintype "passive"))
      (node (ref "X3") (pin "C12") (pinfunction "C12_C12") (pintype "passive"))
      (node (ref "X4") (pin "C12") (pinfunction "C12_C12") (pintype "passive"))
      (node (ref "X5") (pin "C12") (pinfunction "C12_C12") (pintype "passive"))
      (node (ref "X6") (pin "C12") (pinfunction "C12_C12") (pintype "passive"))
    )
    (net (code "38") (name "PI_TXD") (class "Default")
      (node (ref "X1") (pin "A12") (pinfunction "A12_A12") (pintype "passive"))
      (node (ref "X2") (pin "A12") (pinfunction "A12_A12") (pintype "passive"))
      (node (ref "X3") (pin "A12") (pinfunction "A12_A12") (pintype "passive"))
      (node (ref "X4") (pin "A12") (pinfunction "A12_A12") (pintype "passive"))
      (node (ref "X5") (pin "A12") (pinfunction "A12_A12") (pintype "passive"))
      (node (ref "X6") (pin "A12") (pinfunction "A12_A12") (pintype "passive"))
    )
    (net (code "39") (name "SPI_CE0") (class "Default")
      (node (ref "SV1") (pin "12") (pinfunction "12_12") (pintype "passive"))
      (node (ref "X1") (pin "A10") (pinfunction "A10_A10") (pintype "passive"))
      (node (ref "X2") (pin "A10") (pinfunction "A10_A10") (pintype "passive"))
      (node (ref "X3") (pin "A10") (pinfunction "A10_A10") (pintype "passive"))
      (node (ref "X4") (pin "A10") (pinfunction "A10_A10") (pintype "passive"))
      (node (ref "X5") (pin "A10") (pinfunction "A10_A10") (pintype "passive"))
      (node (ref "X6") (pin "A10") (pinfunction "A10_A10") (pintype "passive"))
    )
    (net (code "40") (name "SPI_CE1") (class "Default")
      (node (ref "SV1") (pin "13") (pinfunction "13_13") (pintype "passive"))
      (node (ref "X1") (pin "C11") (pinfunction "C11_C11") (pintype "passive"))
      (node (ref "X2") (pin "C11") (pinfunction "C11_C11") (pintype "passive"))
      (node (ref "X3") (pin "C11") (pinfunction "C11_C11") (pintype "passive"))
      (node (ref "X4") (pin "C11") (pinfunction "C11_C11") (pintype "passive"))
      (node (ref "X5") (pin "C11") (pinfunction "C11_C11") (pintype "passive"))
      (node (ref "X6") (pin "C11") (pinfunction "C11_C11") (pintype "passive"))
    )
    (net (code "41") (name "SPI_MISO") (class "Default")
      (node (ref "SV1") (pin "10") (pinfunction "10_10") (pintype "passive"))
      (node (ref "X1") (pin "A9") (pinfunction "A9_A9") (pintype "passive"))
      (node (ref "X2") (pin "A9") (pinfunction "A9_A9") (pintype "passive"))
      (node (ref "X3") (pin "A9") (pinfunction "A9_A9") (pintype "passive"))
      (node (ref "X4") (pin "A9") (pinfunction "A9_A9") (pintype "passive"))
      (node (ref "X5") (pin "A9") (pinfunction "A9_A9") (pintype "passive"))
      (node (ref "X6") (pin "A9") (pinfunction "A9_A9") (pintype "passive"))
    )
    (net (code "42") (name "SPI_MOSI") (class "Default")
      (node (ref "SV1") (pin "9") (pinfunction "9_9") (pintype "passive"))
      (node (ref "X1") (pin "C9") (pinfunction "C9_C9") (pintype "passive"))
      (node (ref "X2") (pin "C9") (pinfunction "C9_C9") (pintype "passive"))
      (node (ref "X3") (pin "C9") (pinfunction "C9_C9") (pintype "passive"))
      (node (ref "X4") (pin "C9") (pinfunction "C9_C9") (pintype "passive"))
      (node (ref "X5") (pin "C9") (pinfunction "C9_C9") (pintype "passive"))
      (node (ref "X6") (pin "C9") (pinfunction "C9_C9") (pintype "passive"))
    )
    (net (code "43") (name "SPI_SCLK") (class "Default")
      (node (ref "SV1") (pin "11") (pinfunction "11_11") (pintype "passive"))
      (node (ref "X1") (pin "C10") (pinfunction "C10_C10") (pintype "passive"))
      (node (ref "X2") (pin "C10") (pinfunction "C10_C10") (pintype "passive"))
      (node (ref "X3") (pin "C10") (pinfunction "C10_C10") (pintype "passive"))
      (node (ref "X4") (pin "C10") (pinfunction "C10_C10") (pintype "passive"))
      (node (ref "X5") (pin "C10") (pinfunction "C10_C10") (pintype "passive"))
      (node (ref "X6") (pin "C10") (pinfunction "C10_C10") (pintype "passive"))
    )
    (net (code "44") (name "~{PI_RESET}") (class "Default")
      (node (ref "X1") (pin "A26") (pinfunction "A26_A26") (pintype "passive"))
      (node (ref "X2") (pin "A26") (pinfunction "A26_A26") (pintype "passive"))
      (node (ref "X3") (pin "A26") (pinfunction "A26_A26") (pintype "passive"))
      (node (ref "X4") (pin "A26") (pinfunction "A26_A26") (pintype "passive"))
      (node (ref "X5") (pin "A26") (pinfunction "A26_A26") (pintype "passive"))
      (node (ref "X6") (pin "A26") (pinfunction "A26_A26") (pintype "passive"))
    )
  )
)
